# CH1_CH2.net
KiCad netlist of a schematic drawn in Altium Designer
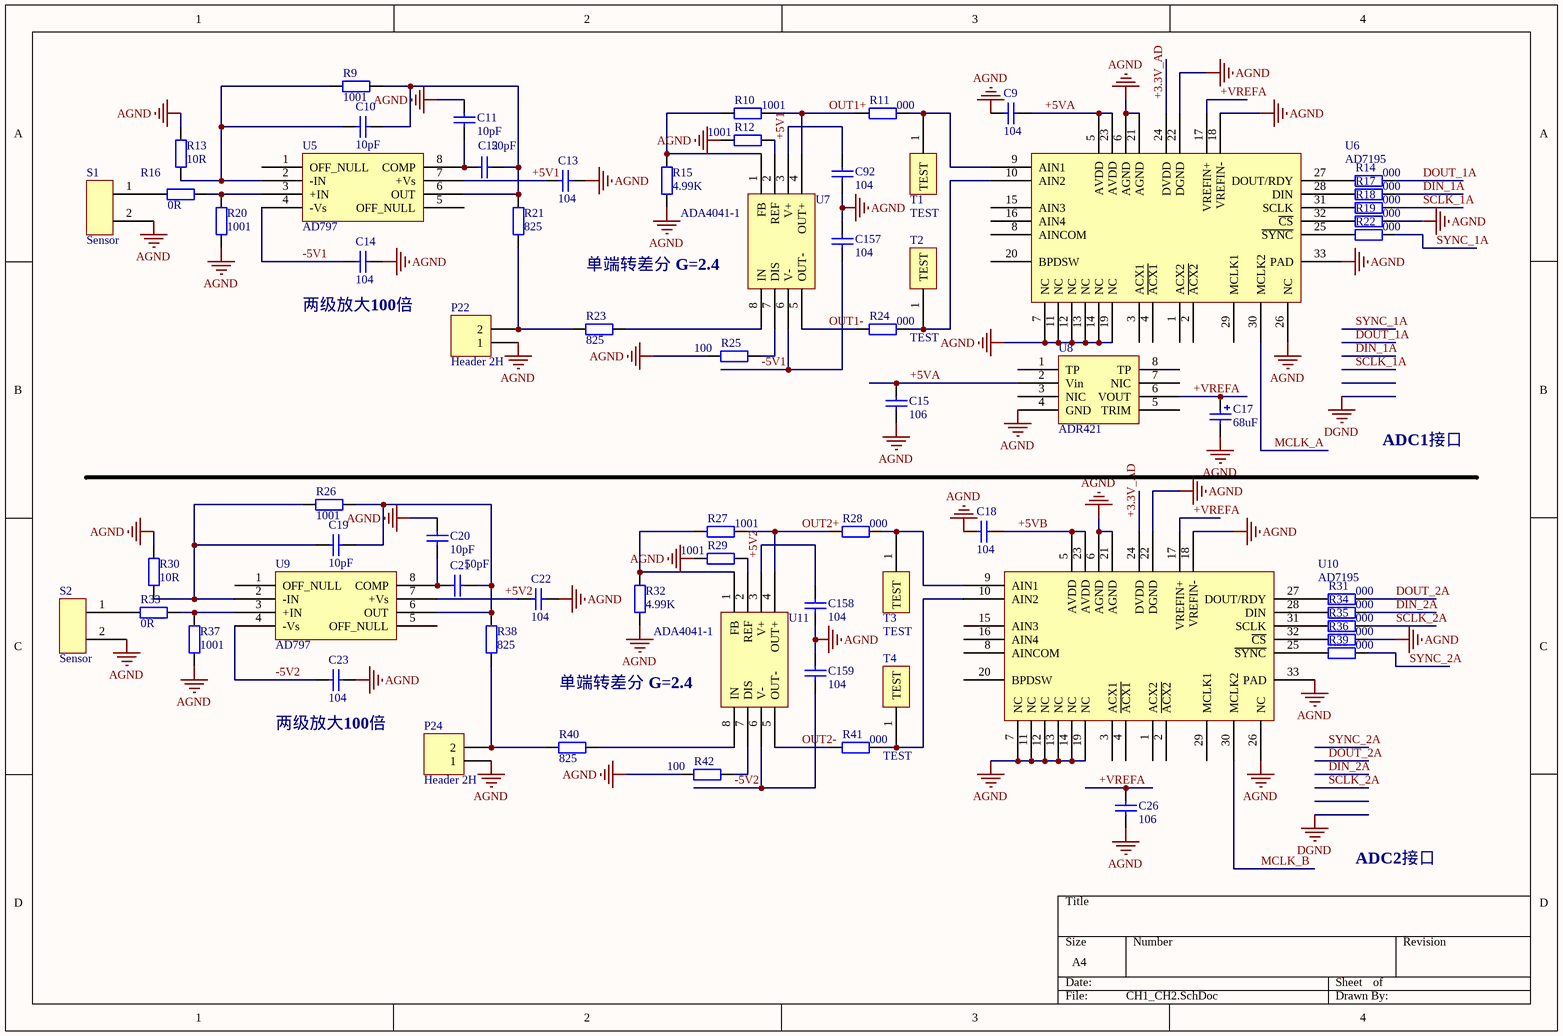
[diagram p0: CH1_CH2.SchDoc]

(export (version "E")
  (design (tool "Eeschema 10.0.6"))
  (components
    (comp (ref "C9")
      (value "104")
      (footprint "0805C")
      (description "Capacitor")
      (fields (field (name "PUBLISHER") "Altium Limited"))
      (libsource (lib "Miscellaneous Devices") (part "Cap"))
    )
    (comp (ref "C10")
      (value "10pF")
      (footprint "0603")
      (description "Capacitor")
      (fields (field (name "PUBLISHER") "Altium Limited"))
      (libsource (lib "Miscellaneous Devices") (part "Cap"))
    )
    (comp (ref "C11")
      (value "10pF")
      (footprint "0603")
      (description "Capacitor")
      (fields (field (name "PUBLISHER") "Altium Limited"))
      (libsource (lib "Miscellaneous Devices") (part "Cap"))
    )
    (comp (ref "C12")
      (value "50pF")
      (footprint "0603")
      (description "Capacitor")
      (fields (field (name "PUBLISHER") "Altium Limited"))
      (libsource (lib "Miscellaneous Devices") (part "Cap"))
    )
    (comp (ref "C13")
      (value "104")
      (footprint "0805C")
      (description "Capacitor")
      (fields (field (name "PUBLISHER") "Altium Limited"))
      (libsource (lib "Miscellaneous Devices") (part "Cap"))
    )
    (comp (ref "C14")
      (value "104")
      (footprint "0805C")
      (description "Capacitor")
      (fields (field (name "PUBLISHER") "Altium Limited"))
      (libsource (lib "Miscellaneous Devices") (part "Cap"))
    )
    (comp (ref "C15")
      (value "106")
      (footprint "0805C")
      (description "Capacitor")
      (fields (field (name "PUBLISHER") "Altium Limited"))
      (libsource (lib "Miscellaneous Devices") (part "Cap"))
    )
    (comp (ref "C17")
      (value "68uF")
      (footprint "6032")
      (description "Polarized Capacitor (Axial)")
      (fields (field (name "PUBLISHER") "Altium Limited"))
      (libsource (lib "Miscellaneous Devices") (part "Cap Pol2"))
    )
    (comp (ref "C18")
      (value "104")
      (footprint "0805C")
      (description "Capacitor")
      (fields (field (name "PUBLISHER") "Altium Limited"))
      (libsource (lib "Miscellaneous Devices") (part "Cap"))
    )
    (comp (ref "C19")
      (value "10pF")
      (footprint "0603")
      (description "Capacitor")
      (fields (field (name "PUBLISHER") "Altium Limited"))
      (libsource (lib "Miscellaneous Devices") (part "Cap"))
    )
    (comp (ref "C20")
      (value "10pF")
      (footprint "0603")
      (description "Capacitor")
      (fields (field (name "PUBLISHER") "Altium Limited"))
      (libsource (lib "Miscellaneous Devices") (part "Cap"))
    )
    (comp (ref "C21")
      (value "50pF")
      (footprint "0603")
      (description "Capacitor")
      (fields (field (name "PUBLISHER") "Altium Limited"))
      (libsource (lib "Miscellaneous Devices") (part "Cap"))
    )
    (comp (ref "C22")
      (value "104")
      (footprint "0805C")
      (description "Capacitor")
      (fields (field (name "PUBLISHER") "Altium Limited"))
      (libsource (lib "Miscellaneous Devices") (part "Cap"))
    )
    (comp (ref "C23")
      (value "104")
      (footprint "0805C")
      (description "Capacitor")
      (fields (field (name "PUBLISHER") "Altium Limited"))
      (libsource (lib "Miscellaneous Devices") (part "Cap"))
    )
    (comp (ref "C26")
      (value "106")
      (footprint "0603")
      (description "Capacitor")
      (fields (field (name "PUBLISHER") "Altium Limited"))
      (libsource (lib "Miscellaneous Devices") (part "Cap"))
    )
    (comp (ref "C92")
      (value "104")
      (footprint "0805C")
      (description "Capacitor")
      (fields (field (name "PUBLISHER") "Altium Limited"))
      (libsource (lib "Miscellaneous Devices") (part "Cap"))
    )
    (comp (ref "C157")
      (value "104")
      (footprint "0805C")
      (description "Capacitor")
      (fields (field (name "PUBLISHER") "Altium Limited"))
      (libsource (lib "Miscellaneous Devices") (part "Cap"))
    )
    (comp (ref "C158")
      (value "104")
      (footprint "0805C")
      (description "Capacitor")
      (fields (field (name "PUBLISHER") "Altium Limited"))
      (libsource (lib "Miscellaneous Devices") (part "Cap"))
    )
    (comp (ref "C159")
      (value "104")
      (footprint "0805C")
      (description "Capacitor")
      (fields (field (name "PUBLISHER") "Altium Limited"))
      (libsource (lib "Miscellaneous Devices") (part "Cap"))
    )
    (comp (ref "P22")
      (value "Header 2H")
      (footprint "HDR1X2")
      (description "Header, 2-Pin, Right Angle")
      (fields (field (name "PUBLISHER") "Altium Limited"))
      (libsource (lib "Miscellaneous Connectors") (part "Header 2H"))
    )
    (comp (ref "P24")
      (value "Header 2H")
      (footprint "HDR1X2")
      (description "Header, 2-Pin, Right Angle")
      (fields (field (name "PUBLISHER") "Altium Limited"))
      (libsource (lib "Miscellaneous Connectors") (part "Header 2H"))
    )
    (comp (ref "R9")
      (value "1001")
      (footprint "0603")
      (description "Resistor")
      (fields (field (name "PUBLISHER") "Altium Limited"))
      (libsource (lib "Miscellaneous Devices") (part "Res2"))
    )
    (comp (ref "R10")
      (value "1001")
      (footprint "0603")
      (description "Resistor")
      (fields (field (name "PUBLISHER") "Altium Limited"))
      (libsource (lib "Miscellaneous Devices") (part "Res2"))
    )
    (comp (ref "R11")
      (value "000")
      (footprint "0603")
      (description "Resistor")
      (fields (field (name "PUBLISHER") "Altium Limited"))
      (libsource (lib "Miscellaneous Devices") (part "Res2"))
    )
    (comp (ref "R12")
      (value "1001")
      (footprint "0603")
      (description "Resistor")
      (fields (field (name "PUBLISHER") "Altium Limited"))
      (libsource (lib "Miscellaneous Devices") (part "Res2"))
    )
    (comp (ref "R13")
      (value "10R")
      (footprint "0603")
      (description "Resistor")
      (fields (field (name "PUBLISHER") "Altium Limited"))
      (libsource (lib "") (part "Res2_2"))
    )
    (comp (ref "R14")
      (value "000")
      (footprint "0603")
      (description "Resistor")
      (fields (field (name "PUBLISHER") "Altium Limited"))
      (libsource (lib "Miscellaneous Devices") (part "Res2"))
    )
    (comp (ref "R15")
      (value "4.99K")
      (footprint "0603")
      (description "Resistor")
      (fields (field (name "PUBLISHER") "Altium Limited"))
      (libsource (lib "") (part "Res2_1"))
    )
    (comp (ref "R16")
      (value "0R")
      (footprint "0603")
      (description "Resistor")
      (fields (field (name "PUBLISHER") "Altium Limited"))
      (libsource (lib "Miscellaneous Devices") (part "Res2"))
    )
    (comp (ref "R17")
      (value "000")
      (footprint "0603")
      (description "Resistor")
      (fields (field (name "PUBLISHER") "Altium Limited"))
      (libsource (lib "Miscellaneous Devices") (part "Res2"))
    )
    (comp (ref "R18")
      (value "000")
      (footprint "0603")
      (description "Resistor")
      (fields (field (name "PUBLISHER") "Altium Limited"))
      (libsource (lib "Miscellaneous Devices") (part "Res2"))
    )
    (comp (ref "R19")
      (value "000")
      (footprint "0603")
      (description "Resistor")
      (fields (field (name "PUBLISHER") "Altium Limited"))
      (libsource (lib "Miscellaneous Devices") (part "Res2"))
    )
    (comp (ref "R20")
      (value "1001")
      (footprint "0603")
      (description "Resistor")
      (fields (field (name "PUBLISHER") "Altium Limited"))
      (libsource (lib "") (part "Res2_1"))
    )
    (comp (ref "R21")
      (value "825")
      (footprint "0603")
      (description "Resistor")
      (fields (field (name "PUBLISHER") "Altium Limited"))
      (libsource (lib "") (part "Res2_1"))
    )
    (comp (ref "R22")
      (value "000")
      (footprint "0603")
      (description "Resistor")
      (fields (field (name "PUBLISHER") "Altium Limited"))
      (libsource (lib "Miscellaneous Devices") (part "Res2"))
    )
    (comp (ref "R23")
      (value "825")
      (footprint "0603")
      (description "Resistor")
      (fields (field (name "PUBLISHER") "Altium Limited"))
      (libsource (lib "Miscellaneous Devices") (part "Res2"))
    )
    (comp (ref "R24")
      (value "000")
      (footprint "0603")
      (description "Resistor")
      (fields (field (name "PUBLISHER") "Altium Limited"))
      (libsource (lib "Miscellaneous Devices") (part "Res2"))
    )
    (comp (ref "R25")
      (value "100")
      (footprint "0603")
      (description "Resistor")
      (fields (field (name "PUBLISHER") "Altium Limited"))
      (libsource (lib "Miscellaneous Devices") (part "Res2"))
    )
    (comp (ref "R26")
      (value "1001")
      (footprint "0603")
      (description "Resistor")
      (fields (field (name "PUBLISHER") "Altium Limited"))
      (libsource (lib "Miscellaneous Devices") (part "Res2"))
    )
    (comp (ref "R27")
      (value "1001")
      (footprint "0603")
      (description "Resistor")
      (fields (field (name "PUBLISHER") "Altium Limited"))
      (libsource (lib "Miscellaneous Devices") (part "Res2"))
    )
    (comp (ref "R28")
      (value "000")
      (footprint "0603")
      (description "Resistor")
      (fields (field (name "PUBLISHER") "Altium Limited"))
      (libsource (lib "Miscellaneous Devices") (part "Res2"))
    )
    (comp (ref "R29")
      (value "1001")
      (footprint "0603")
      (description "Resistor")
      (fields (field (name "PUBLISHER") "Altium Limited"))
      (libsource (lib "Miscellaneous Devices") (part "Res2"))
    )
    (comp (ref "R30")
      (value "10R")
      (footprint "0603")
      (description "Resistor")
      (fields (field (name "PUBLISHER") "Altium Limited"))
      (libsource (lib "") (part "Res2_2"))
    )
    (comp (ref "R31")
      (value "000")
      (footprint "0603")
      (description "Resistor")
      (fields (field (name "PUBLISHER") "Altium Limited"))
      (libsource (lib "Miscellaneous Devices") (part "Res2"))
    )
    (comp (ref "R32")
      (value "4.99K")
      (footprint "0603")
      (description "Resistor")
      (fields (field (name "PUBLISHER") "Altium Limited"))
      (libsource (lib "") (part "Res2_1"))
    )
    (comp (ref "R33")
      (value "0R")
      (footprint "0603")
      (description "Resistor")
      (fields (field (name "PUBLISHER") "Altium Limited"))
      (libsource (lib "Miscellaneous Devices") (part "Res2"))
    )
    (comp (ref "R34")
      (value "000")
      (footprint "0603")
      (description "Resistor")
      (fields (field (name "PUBLISHER") "Altium Limited"))
      (libsource (lib "Miscellaneous Devices") (part "Res2"))
    )
    (comp (ref "R35")
      (value "000")
      (footprint "0603")
      (description "Resistor")
      (fields (field (name "PUBLISHER") "Altium Limited"))
      (libsource (lib "Miscellaneous Devices") (part "Res2"))
    )
    (comp (ref "R36")
      (value "000")
      (footprint "0603")
      (description "Resistor")
      (fields (field (name "PUBLISHER") "Altium Limited"))
      (libsource (lib "Miscellaneous Devices") (part "Res2"))
    )
    (comp (ref "R37")
      (value "1001")
      (footprint "0603")
      (description "Resistor")
      (fields (field (name "PUBLISHER") "Altium Limited"))
      (libsource (lib "") (part "Res2_1"))
    )
    (comp (ref "R38")
      (value "825")
      (footprint "0603")
      (description "Resistor")
      (fields (field (name "PUBLISHER") "Altium Limited"))
      (libsource (lib "") (part "Res2_1"))
    )
    (comp (ref "R39")
      (value "000")
      (footprint "0603")
      (description "Resistor")
      (fields (field (name "PUBLISHER") "Altium Limited"))
      (libsource (lib "Miscellaneous Devices") (part "Res2"))
    )
    (comp (ref "R40")
      (value "825")
      (footprint "0603")
      (description "Resistor")
      (fields (field (name "PUBLISHER") "Altium Limited"))
      (libsource (lib "Miscellaneous Devices") (part "Res2"))
    )
    (comp (ref "R41")
      (value "000")
      (footprint "0603")
      (description "Resistor")
      (fields (field (name "PUBLISHER") "Altium Limited"))
      (libsource (lib "Miscellaneous Devices") (part "Res2"))
    )
    (comp (ref "R42")
      (value "100")
      (footprint "0603")
      (description "Resistor")
      (fields (field (name "PUBLISHER") "Altium Limited"))
      (libsource (lib "Miscellaneous Devices") (part "Res2"))
    )
    (comp (ref "S1") (value "Sensor") (footprint "HDR1X2") (libsource (lib "Schlib1") (part "Sensor")))
    (comp (ref "S2") (value "Sensor") (footprint "HDR1X2") (libsource (lib "Schlib1") (part "Sensor")))
    (comp (ref "T1") (value "TEST") (footprint "TEST") (libsource (lib "Schlib1") (part "TEST")))
    (comp (ref "T2") (value "TEST") (footprint "TEST") (libsource (lib "") (part "TEST_1")))
    (comp (ref "T3") (value "TEST") (footprint "TEST") (libsource (lib "Schlib1") (part "TEST")))
    (comp (ref "T4") (value "TEST") (footprint "TEST") (libsource (lib "") (part "TEST_1")))
    (comp (ref "U5") (value "AD797") (footprint "SO8") (libsource (lib "Schlib1") (part "AD797")))
    (comp (ref "U6") (value "AD7195") (footprint "VQFN32") (libsource (lib "Schlib1") (part "AD7195")))
    (comp (ref "U7") (value "ADA4041-1") (footprint "SO8") (libsource (lib "Schlib1") (part "ADA4041-1")))
    (comp (ref "U8") (value "ADR421") (footprint "SO8") (libsource (lib "Schlib1") (part "ADR421")))
    (comp (ref "U9") (value "AD797") (footprint "SO8") (libsource (lib "Schlib1") (part "AD797")))
    (comp (ref "U10") (value "AD7195") (footprint "VQFN32") (libsource (lib "Schlib1") (part "AD7195")))
    (comp (ref "U11") (value "ADA4041-1") (footprint "SO8") (libsource (lib "Schlib1") (part "ADA4041-1")))
  )
  (nets
    (net (code "1") (name "/+3.3V_AD") (class "Default")
      (node (ref "U10") (pin "24") (pinfunction "DVDD_24") (pintype "passive"))
      (node (ref "U6") (pin "24") (pinfunction "DVDD_24") (pintype "passive"))
    )
    (net (code "2") (name "/+5V1") (class "Default")
      (node (ref "C13") (pin "2") (pinfunction "2_2") (pintype "passive"))
      (node (ref "C92") (pin "1") (pinfunction "1_1") (pintype "passive"))
      (node (ref "U5") (pin "7") (pinfunction "+Vs_7") (pintype "passive"))
      (node (ref "U7") (pin "3") (pinfunction "V+_3") (pintype "passive"))
    )
    (net (code "3") (name "/+5V2") (class "Default")
      (node (ref "C158") (pin "1") (pinfunction "1_1") (pintype "passive"))
      (node (ref "C22") (pin "2") (pinfunction "2_2") (pintype "passive"))
      (node (ref "U11") (pin "3") (pinfunction "V+_3") (pintype "passive"))
      (node (ref "U9") (pin "7") (pinfunction "+Vs_7") (pintype "passive"))
    )
    (net (code "4") (name "/+5VA") (class "Default")
      (node (ref "C15") (pin "1") (pinfunction "1_1") (pintype "passive"))
      (node (ref "C9") (pin "2") (pinfunction "2_2") (pintype "passive"))
      (node (ref "U6") (pin "23") (pinfunction "AVDD_23") (pintype "passive"))
      (node (ref "U6") (pin "5") (pinfunction "AVDD_5") (pintype "passive"))
      (node (ref "U8") (pin "2") (pinfunction "Vin_2") (pintype "passive"))
    )
    (net (code "5") (name "/+5VB") (class "Default")
      (node (ref "C18") (pin "2") (pinfunction "2_2") (pintype "passive"))
      (node (ref "U10") (pin "23") (pinfunction "AVDD_23") (pintype "passive"))
      (node (ref "U10") (pin "5") (pinfunction "AVDD_5") (pintype "passive"))
    )
    (net (code "6") (name "/+VREFA") (class "Default")
      (node (ref "C17") (pin "1") (pinfunction "1_1") (pintype "passive"))
      (node (ref "C26") (pin "1") (pinfunction "1_1") (pintype "passive"))
      (node (ref "U10") (pin "17") (pinfunction "VREFIN+_17") (pintype "passive"))
      (node (ref "U6") (pin "17") (pinfunction "VREFIN+_17") (pintype "passive"))
      (node (ref "U8") (pin "6") (pinfunction "VOUT_6") (pintype "passive"))
    )
    (net (code "7") (name "/-5V1") (class "Default")
      (node (ref "C14") (pin "2") (pinfunction "2_2") (pintype "passive"))
      (node (ref "C157") (pin "2") (pinfunction "2_2") (pintype "passive"))
      (node (ref "U5") (pin "4") (pinfunction "-Vs_4") (pintype "passive"))
      (node (ref "U7") (pin "6") (pinfunction "V-_6") (pintype "passive"))
    )
    (net (code "8") (name "/-5V2") (class "Default")
      (node (ref "C159") (pin "2") (pinfunction "2_2") (pintype "passive"))
      (node (ref "C23") (pin "2") (pinfunction "2_2") (pintype "passive"))
      (node (ref "U11") (pin "6") (pinfunction "V-_6") (pintype "passive"))
      (node (ref "U9") (pin "4") (pinfunction "-Vs_4") (pintype "passive"))
    )
    (net (code "9") (name "/DIN_1A") (class "Default")
      (node (ref "R17") (pin "2") (pinfunction "2_2") (pintype "passive"))
    )
    (net (code "10") (name "/DIN_2A") (class "Default")
      (node (ref "R34") (pin "2") (pinfunction "2_2") (pintype "passive"))
    )
    (net (code "11") (name "/DOUT_1A") (class "Default")
      (node (ref "R14") (pin "2") (pinfunction "2_2") (pintype "passive"))
    )
    (net (code "12") (name "/DOUT_2A") (class "Default")
      (node (ref "R31") (pin "2") (pinfunction "2_2") (pintype "passive"))
    )
    (net (code "13") (name "/MCLK_A") (class "Default")
      (node (ref "U6") (pin "30") (pinfunction "MCLK2_30") (pintype "passive"))
    )
    (net (code "14") (name "/MCLK_B") (class "Default")
      (node (ref "U10") (pin "30") (pinfunction "MCLK2_30") (pintype "passive"))
    )
    (net (code "15") (name "/OUT1+") (class "Default")
      (node (ref "R10") (pin "2") (pinfunction "2_2") (pintype "passive"))
      (node (ref "R11") (pin "1") (pinfunction "1_1") (pintype "passive"))
      (node (ref "U7") (pin "4") (pinfunction "OUT+_4") (pintype "passive"))
    )
    (net (code "16") (name "/OUT1-") (class "Default")
      (node (ref "R24") (pin "1") (pinfunction "1_1") (pintype "passive"))
      (node (ref "U7") (pin "5") (pinfunction "OUT-_5") (pintype "passive"))
    )
    (net (code "17") (name "/OUT2+") (class "Default")
      (node (ref "R27") (pin "2") (pinfunction "2_2") (pintype "passive"))
      (node (ref "R28") (pin "1") (pinfunction "1_1") (pintype "passive"))
      (node (ref "U11") (pin "4") (pinfunction "OUT+_4") (pintype "passive"))
    )
    (net (code "18") (name "/OUT2-") (class "Default")
      (node (ref "R41") (pin "1") (pinfunction "1_1") (pintype "passive"))
      (node (ref "U11") (pin "5") (pinfunction "OUT-_5") (pintype "passive"))
    )
    (net (code "19") (name "/SCLK_1A") (class "Default")
      (node (ref "R18") (pin "2") (pinfunction "2_2") (pintype "passive"))
    )
    (net (code "20") (name "/SCLK_2A") (class "Default")
      (node (ref "R35") (pin "2") (pinfunction "2_2") (pintype "passive"))
    )
    (net (code "21") (name "/SYNC_1A") (class "Default")
      (node (ref "R22") (pin "2") (pinfunction "2_2") (pintype "passive"))
    )
    (net (code "22") (name "/SYNC_2A") (class "Default")
      (node (ref "R39") (pin "2") (pinfunction "2_2") (pintype "passive"))
    )
    (net (code "23") (name "AGND") (class "Default")
      (node (ref "C11") (pin "2") (pinfunction "2_2") (pintype "passive"))
      (node (ref "C13") (pin "1") (pinfunction "1_1") (pintype "passive"))
      (node (ref "C14") (pin "1") (pinfunction "1_1") (pintype "passive"))
      (node (ref "C15") (pin "2") (pinfunction "2_2") (pintype "passive"))
      (node (ref "C157") (pin "1") (pinfunction "1_1") (pintype "passive"))
      (node (ref "C158") (pin "2") (pinfunction "2_2") (pintype "passive"))
      (node (ref "C159") (pin "1") (pinfunction "1_1") (pintype "passive"))
      (node (ref "C17") (pin "2") (pinfunction "2_2") (pintype "passive"))
      (node (ref "C18") (pin "1") (pinfunction "1_1") (pintype "passive"))
      (node (ref "C20") (pin "2") (pinfunction "2_2") (pintype "passive"))
      (node (ref "C22") (pin "1") (pinfunction "1_1") (pintype "passive"))
      (node (ref "C23") (pin "1") (pinfunction "1_1") (pintype "passive"))
      (node (ref "C26") (pin "2") (pinfunction "2_2") (pintype "passive"))
      (node (ref "C9") (pin "1") (pinfunction "1_1") (pintype "passive"))
      (node (ref "C92") (pin "2") (pinfunction "2_2") (pintype "passive"))
      (node (ref "P22") (pin "1") (pinfunction "1_1") (pintype "passive"))
      (node (ref "P24") (pin "1") (pinfunction "1_1") (pintype "passive"))
      (node (ref "R12") (pin "1") (pinfunction "1_1") (pintype "passive"))
      (node (ref "R13") (pin "1") (pinfunction "1_1") (pintype "passive"))
      (node (ref "R15") (pin "1") (pinfunction "1_1") (pintype "passive"))
      (node (ref "R19") (pin "2") (pinfunction "2_2") (pintype "passive"))
      (node (ref "R20") (pin "1") (pinfunction "1_1") (pintype "passive"))
      (node (ref "R25") (pin "1") (pinfunction "1_1") (pintype "passive"))
      (node (ref "R29") (pin "1") (pinfunction "1_1") (pintype "passive"))
      (node (ref "R30") (pin "1") (pinfunction "1_1") (pintype "passive"))
      (node (ref "R32") (pin "1") (pinfunction "1_1") (pintype "passive"))
      (node (ref "R36") (pin "2") (pinfunction "2_2") (pintype "passive"))
      (node (ref "R37") (pin "1") (pinfunction "1_1") (pintype "passive"))
      (node (ref "R42") (pin "1") (pinfunction "1_1") (pintype "passive"))
      (node (ref "S1") (pin "2") (pinfunction "2_2") (pintype "passive"))
      (node (ref "S2") (pin "2") (pinfunction "2_2") (pintype "passive"))
      (node (ref "U10") (pin "11") (pinfunction "NC_11") (pintype "passive"))
      (node (ref "U10") (pin "12") (pinfunction "NC_12") (pintype "passive"))
      (node (ref "U10") (pin "13") (pinfunction "NC_13") (pintype "passive"))
      (node (ref "U10") (pin "14") (pinfunction "NC_14") (pintype "passive"))
      (node (ref "U10") (pin "18") (pinfunction "VREFIN-_18") (pintype "passive"))
      (node (ref "U10") (pin "19") (pinfunction "NC_19") (pintype "passive"))
      (node (ref "U10") (pin "21") (pinfunction "AGND_21") (pintype "passive"))
      (node (ref "U10") (pin "22") (pinfunction "DGND_22") (pintype "passive"))
      (node (ref "U10") (pin "26") (pinfunction "NC_26") (pintype "passive"))
      (node (ref "U10") (pin "33") (pinfunction "PAD_33") (pintype "passive"))
      (node (ref "U10") (pin "6") (pinfunction "AGND_6") (pintype "passive"))
      (node (ref "U10") (pin "7") (pinfunction "NC_7") (pintype "passive"))
      (node (ref "U6") (pin "11") (pinfunction "NC_11") (pintype "passive"))
      (node (ref "U6") (pin "12") (pinfunction "NC_12") (pintype "passive"))
      (node (ref "U6") (pin "13") (pinfunction "NC_13") (pintype "passive"))
      (node (ref "U6") (pin "14") (pinfunction "NC_14") (pintype "passive"))
      (node (ref "U6") (pin "18") (pinfunction "VREFIN-_18") (pintype "passive"))
      (node (ref "U6") (pin "19") (pinfunction "NC_19") (pintype "passive"))
      (node (ref "U6") (pin "21") (pinfunction "AGND_21") (pintype "passive"))
      (node (ref "U6") (pin "22") (pinfunction "DGND_22") (pintype "passive"))
      (node (ref "U6") (pin "26") (pinfunction "NC_26") (pintype "passive"))
      (node (ref "U6") (pin "33") (pinfunction "PAD_33") (pintype "passive"))
      (node (ref "U6") (pin "6") (pinfunction "AGND_6") (pintype "passive"))
      (node (ref "U6") (pin "7") (pinfunction "NC_7") (pintype "passive"))
      (node (ref "U8") (pin "4") (pinfunction "GND_4") (pintype "passive"))
    )
    (net (code "25") (name "Net-(P22-Pad2)") (class "Default")
      (node (ref "P22") (pin "2") (pinfunction "2_2") (pintype "passive"))
      (node (ref "R21") (pin "1") (pinfunction "1_1") (pintype "passive"))
      (node (ref "R23") (pin "1") (pinfunction "1_1") (pintype "passive"))
    )
    (net (code "26") (name "Net-(P24-Pad2)") (class "Default")
      (node (ref "P24") (pin "2") (pinfunction "2_2") (pintype "passive"))
      (node (ref "R38") (pin "1") (pinfunction "1_1") (pintype "passive"))
      (node (ref "R40") (pin "1") (pinfunction "1_1") (pintype "passive"))
    )
    (net (code "27") (name "Net-(R16-Pad1)") (class "Default")
      (node (ref "R16") (pin "1") (pinfunction "1_1") (pintype "passive"))
      (node (ref "S1") (pin "1") (pinfunction "1_1") (pintype "passive"))
    )
    (net (code "28") (name "Net-(R33-Pad1)") (class "Default")
      (node (ref "R33") (pin "1") (pinfunction "1_1") (pintype "passive"))
      (node (ref "S2") (pin "1") (pinfunction "1_1") (pintype "passive"))
    )
    (net (code "29") (name "Net-(T1-TEST)") (class "Default")
      (node (ref "R11") (pin "2") (pinfunction "2_2") (pintype "passive"))
      (node (ref "T1") (pin "1") (pinfunction "TEST_1") (pintype "passive"))
      (node (ref "U6") (pin "9") (pinfunction "AIN1_9") (pintype "passive"))
    )
    (net (code "30") (name "Net-(T2-TEST)") (class "Default")
      (node (ref "R24") (pin "2") (pinfunction "2_2") (pintype "passive"))
      (node (ref "T2") (pin "1") (pinfunction "TEST_1") (pintype "passive"))
      (node (ref "U6") (pin "10") (pinfunction "AIN2_10") (pintype "passive"))
    )
    (net (code "31") (name "Net-(T3-TEST)") (class "Default")
      (node (ref "R28") (pin "2") (pinfunction "2_2") (pintype "passive"))
      (node (ref "T3") (pin "1") (pinfunction "TEST_1") (pintype "passive"))
      (node (ref "U10") (pin "9") (pinfunction "AIN1_9") (pintype "passive"))
    )
    (net (code "32") (name "Net-(T4-TEST)") (class "Default")
      (node (ref "R41") (pin "2") (pinfunction "2_2") (pintype "passive"))
      (node (ref "T4") (pin "1") (pinfunction "TEST_1") (pintype "passive"))
      (node (ref "U10") (pin "10") (pinfunction "AIN2_10") (pintype "passive"))
    )
    (net (code "33") (name "Net-(U5-+IN)") (class "Default")
      (node (ref "R16") (pin "2") (pinfunction "2_2") (pintype "passive"))
      (node (ref "R20") (pin "2") (pinfunction "2_2") (pintype "passive"))
      (node (ref "U5") (pin "3") (pinfunction "+IN_3") (pintype "passive"))
    )
    (net (code "34") (name "Net-(U5--IN)") (class "Default")
      (node (ref "C10") (pin "2") (pinfunction "2_2") (pintype "passive"))
      (node (ref "R13") (pin "2") (pinfunction "2_2") (pintype "passive"))
      (node (ref "R9") (pin "1") (pinfunction "1_1") (pintype "passive"))
      (node (ref "U5") (pin "2") (pinfunction "-IN_2") (pintype "passive"))
    )
    (net (code "35") (name "Net-(U5-COMP)") (class "Default")
      (node (ref "C11") (pin "1") (pinfunction "1_1") (pintype "passive"))
      (node (ref "C12") (pin "2") (pinfunction "2_2") (pintype "passive"))
      (node (ref "U5") (pin "8") (pinfunction "COMP_8") (pintype "passive"))
    )
    (net (code "36") (name "Net-(U5-OUT)") (class "Default")
      (node (ref "C10") (pin "1") (pinfunction "1_1") (pintype "passive"))
      (node (ref "C12") (pin "1") (pinfunction "1_1") (pintype "passive"))
      (node (ref "R21") (pin "2") (pinfunction "2_2") (pintype "passive"))
      (node (ref "R9") (pin "2") (pinfunction "2_2") (pintype "passive"))
      (node (ref "U5") (pin "6") (pinfunction "OUT_6") (pintype "passive"))
    )
    (net (code "37") (name "Net-(U6-DIN)") (class "Default")
      (node (ref "R17") (pin "1") (pinfunction "1_1") (pintype "passive"))
      (node (ref "U6") (pin "28") (pinfunction "DIN_28") (pintype "passive"))
    )
    (net (code "38") (name "Net-(U6-DOUT{slash}RDY)") (class "Default")
      (node (ref "R14") (pin "1") (pinfunction "1_1") (pintype "passive"))
      (node (ref "U6") (pin "27") (pinfunction "DOUT/RDY_27") (pintype "passive"))
    )
    (net (code "39") (name "Net-(U6-SCLK)") (class "Default")
      (node (ref "R18") (pin "1") (pinfunction "1_1") (pintype "passive"))
      (node (ref "U6") (pin "31") (pinfunction "SCLK_31") (pintype "passive"))
    )
    (net (code "40") (name "Net-(U6-~{CS})") (class "Default")
      (node (ref "R19") (pin "1") (pinfunction "1_1") (pintype "passive"))
      (node (ref "U6") (pin "32") (pinfunction "~{CS}_32") (pintype "passive"))
    )
    (net (code "41") (name "Net-(U6-~{SYNC})") (class "Default")
      (node (ref "R22") (pin "1") (pinfunction "1_1") (pintype "passive"))
      (node (ref "U6") (pin "25") (pinfunction "~{SYNC}_25") (pintype "passive"))
    )
    (net (code "42") (name "Net-(U7-DIS)") (class "Default")
      (node (ref "R25") (pin "2") (pinfunction "2_2") (pintype "passive"))
      (node (ref "U7") (pin "7") (pinfunction "DIS_7") (pintype "passive"))
    )
    (net (code "43") (name "Net-(U7-FB)") (class "Default")
      (node (ref "R10") (pin "1") (pinfunction "1_1") (pintype "passive"))
      (node (ref "R15") (pin "2") (pinfunction "2_2") (pintype "passive"))
      (node (ref "U7") (pin "1") (pinfunction "FB_1") (pintype "passive"))
    )
    (net (code "44") (name "Net-(U7-IN)") (class "Default")
      (node (ref "R23") (pin "2") (pinfunction "2_2") (pintype "passive"))
      (node (ref "U7") (pin "8") (pinfunction "IN_8") (pintype "passive"))
    )
    (net (code "45") (name "Net-(U7-REF)") (class "Default")
      (node (ref "R12") (pin "2") (pinfunction "2_2") (pintype "passive"))
      (node (ref "U7") (pin "2") (pinfunction "REF_2") (pintype "passive"))
    )
    (net (code "46") (name "Net-(U9-+IN)") (class "Default")
      (node (ref "R33") (pin "2") (pinfunction "2_2") (pintype "passive"))
      (node (ref "R37") (pin "2") (pinfunction "2_2") (pintype "passive"))
      (node (ref "U9") (pin "3") (pinfunction "+IN_3") (pintype "passive"))
    )
    (net (code "47") (name "Net-(U9--IN)") (class "Default")
      (node (ref "C19") (pin "2") (pinfunction "2_2") (pintype "passive"))
      (node (ref "R26") (pin "1") (pinfunction "1_1") (pintype "passive"))
      (node (ref "R30") (pin "2") (pinfunction "2_2") (pintype "passive"))
      (node (ref "U9") (pin "2") (pinfunction "-IN_2") (pintype "passive"))
    )
    (net (code "48") (name "Net-(U9-COMP)") (class "Default")
      (node (ref "C20") (pin "1") (pinfunction "1_1") (pintype "passive"))
      (node (ref "C21") (pin "2") (pinfunction "2_2") (pintype "passive"))
      (node (ref "U9") (pin "8") (pinfunction "COMP_8") (pintype "passive"))
    )
    (net (code "49") (name "Net-(U9-OUT)") (class "Default")
      (node (ref "C19") (pin "1") (pinfunction "1_1") (pintype "passive"))
      (node (ref "C21") (pin "1") (pinfunction "1_1") (pintype "passive"))
      (node (ref "R26") (pin "2") (pinfunction "2_2") (pintype "passive"))
      (node (ref "R38") (pin "2") (pinfunction "2_2") (pintype "passive"))
      (node (ref "U9") (pin "6") (pinfunction "OUT_6") (pintype "passive"))
    )
    (net (code "50") (name "Net-(U10-DIN)") (class "Default")
      (node (ref "R34") (pin "1") (pinfunction "1_1") (pintype "passive"))
      (node (ref "U10") (pin "28") (pinfunction "DIN_28") (pintype "passive"))
    )
    (net (code "51") (name "Net-(U10-DOUT{slash}RDY)") (class "Default")
      (node (ref "R31") (pin "1") (pinfunction "1_1") (pintype "passive"))
      (node (ref "U10") (pin "27") (pinfunction "DOUT/RDY_27") (pintype "passive"))
    )
    (net (code "52") (name "Net-(U10-SCLK)") (class "Default")
      (node (ref "R35") (pin "1") (pinfunction "1_1") (pintype "passive"))
      (node (ref "U10") (pin "31") (pinfunction "SCLK_31") (pintype "passive"))
    )
    (net (code "53") (name "Net-(U10-~{CS})") (class "Default")
      (node (ref "R36") (pin "1") (pinfunction "1_1") (pintype "passive"))
      (node (ref "U10") (pin "32") (pinfunction "~{CS}_32") (pintype "passive"))
    )
    (net (code "54") (name "Net-(U10-~{SYNC})") (class "Default")
      (node (ref "R39") (pin "1") (pinfunction "1_1") (pintype "passive"))
      (node (ref "U10") (pin "25") (pinfunction "~{SYNC}_25") (pintype "passive"))
    )
    (net (code "55") (name "Net-(U11-DIS)") (class "Default")
      (node (ref "R42") (pin "2") (pinfunction "2_2") (pintype "passive"))
      (node (ref "U11") (pin "7") (pinfunction "DIS_7") (pintype "passive"))
    )
    (net (code "56") (name "Net-(U11-FB)") (class "Default")
      (node (ref "R27") (pin "1") (pinfunction "1_1") (pintype "passive"))
      (node (ref "R32") (pin "2") (pinfunction "2_2") (pintype "passive"))
      (node (ref "U11") (pin "1") (pinfunction "FB_1") (pintype "passive"))
    )
    (net (code "57") (name "Net-(U11-IN)") (class "Default")
      (node (ref "R40") (pin "2") (pinfunction "2_2") (pintype "passive"))
      (node (ref "U11") (pin "8") (pinfunction "IN_8") (pintype "passive"))
    )
    (net (code "58") (name "Net-(U11-REF)") (class "Default")
      (node (ref "R29") (pin "2") (pinfunction "2_2") (pintype "passive"))
      (node (ref "U11") (pin "2") (pinfunction "REF_2") (pintype "passive"))
    )
    (net (code "59") (name "unconnected-(U5-OFF_NULL-Pad1)") (class "Default")
      (node (ref "U5") (pin "1") (pinfunction "OFF_NULL_1") (pintype "passive"))
    )
    (net (code "60") (name "unconnected-(U5-OFF_NULL-Pad5)") (class "Default")
      (node (ref "U5") (pin "5") (pinfunction "OFF_NULL_5") (pintype "passive"))
    )
    (net (code "61") (name "unconnected-(U6-ACX1-Pad3)") (class "Default")
      (node (ref "U6") (pin "3") (pinfunction "ACX1_3") (pintype "passive"))
    )
    (net (code "62") (name "unconnected-(U6-ACX2-Pad1)") (class "Default")
      (node (ref "U6") (pin "1") (pinfunction "ACX2_1") (pintype "passive"))
    )
    (net (code "63") (name "unconnected-(U6-AIN3-Pad15)") (class "Default")
      (node (ref "U6") (pin "15") (pinfunction "AIN3_15") (pintype "passive"))
    )
    (net (code "64") (name "unconnected-(U6-AIN4-Pad16)") (class "Default")
      (node (ref "U6") (pin "16") (pinfunction "AIN4_16") (pintype "passive"))
    )
    (net (code "65") (name "unconnected-(U6-AINCOM-Pad8)") (class "Default")
      (node (ref "U6") (pin "8") (pinfunction "AINCOM_8") (pintype "passive"))
    )
    (net (code "66") (name "unconnected-(U6-BPDSW-Pad20)") (class "Default")
      (node (ref "U6") (pin "20") (pinfunction "BPDSW_20") (pintype "passive"))
    )
    (net (code "67") (name "unconnected-(U6-MCLK1-Pad29)") (class "Default")
      (node (ref "U6") (pin "29") (pinfunction "MCLK1_29") (pintype "passive"))
    )
    (net (code "68") (name "unconnected-(U6-~{ACX1}-Pad4)") (class "Default")
      (node (ref "U6") (pin "4") (pinfunction "~{ACX1}_4") (pintype "passive"))
    )
    (net (code "69") (name "unconnected-(U6-~{ACX2}-Pad2)") (class "Default")
      (node (ref "U6") (pin "2") (pinfunction "~{ACX2}_2") (pintype "passive"))
    )
    (net (code "70") (name "unconnected-(U8-NIC-Pad3)") (class "Default")
      (node (ref "U8") (pin "3") (pinfunction "NIC_3") (pintype "passive"))
    )
    (net (code "71") (name "unconnected-(U8-NIC-Pad7)") (class "Default")
      (node (ref "U8") (pin "7") (pinfunction "NIC_7") (pintype "passive"))
    )
    (net (code "72") (name "unconnected-(U8-TP-Pad1)") (class "Default")
      (node (ref "U8") (pin "1") (pinfunction "TP_1") (pintype "passive"))
    )
    (net (code "73") (name "unconnected-(U8-TP-Pad8)") (class "Default")
      (node (ref "U8") (pin "8") (pinfunction "TP_8") (pintype "passive"))
    )
    (net (code "74") (name "unconnected-(U8-TRIM-Pad5)") (class "Default")
      (node (ref "U8") (pin "5") (pinfunction "TRIM_5") (pintype "passive"))
    )
    (net (code "75") (name "unconnected-(U9-OFF_NULL-Pad1)") (class "Default")
      (node (ref "U9") (pin "1") (pinfunction "OFF_NULL_1") (pintype "passive"))
    )
    (net (code "76") (name "unconnected-(U9-OFF_NULL-Pad5)") (class "Default")
      (node (ref "U9") (pin "5") (pinfunction "OFF_NULL_5") (pintype "passive"))
    )
    (net (code "77") (name "unconnected-(U10-ACX1-Pad3)") (class "Default")
      (node (ref "U10") (pin "3") (pinfunction "ACX1_3") (pintype "passive"))
    )
    (net (code "78") (name "unconnected-(U10-ACX2-Pad1)") (class "Default")
      (node (ref "U10") (pin "1") (pinfunction "ACX2_1") (pintype "passive"))
    )
    (net (code "79") (name "unconnected-(U10-AIN3-Pad15)") (class "Default")
      (node (ref "U10") (pin "15") (pinfunction "AIN3_15") (pintype "passive"))
    )
    (net (code "80") (name "unconnected-(U10-AIN4-Pad16)") (class "Default")
      (node (ref "U10") (pin "16") (pinfunction "AIN4_16") (pintype "passive"))
    )
    (net (code "81") (name "unconnected-(U10-AINCOM-Pad8)") (class "Default")
      (node (ref "U10") (pin "8") (pinfunction "AINCOM_8") (pintype "passive"))
    )
    (net (code "82") (name "unconnected-(U10-BPDSW-Pad20)") (class "Default")
      (node (ref "U10") (pin "20") (pinfunction "BPDSW_20") (pintype "passive"))
    )
    (net (code "83") (name "unconnected-(U10-MCLK1-Pad29)") (class "Default")
      (node (ref "U10") (pin "29") (pinfunction "MCLK1_29") (pintype "passive"))
    )
    (net (code "84") (name "unconnected-(U10-~{ACX1}-Pad4)") (class "Default")
      (node (ref "U10") (pin "4") (pinfunction "~{ACX1}_4") (pintype "passive"))
    )
    (net (code "85") (name "unconnected-(U10-~{ACX2}-Pad2)") (class "Default")
      (node (ref "U10") (pin "2") (pinfunction "~{ACX2}_2") (pintype "passive"))
    )
  )
)
